# usbkeyboard1.net
KiCad netlist of a schematic drawn in EAGLE
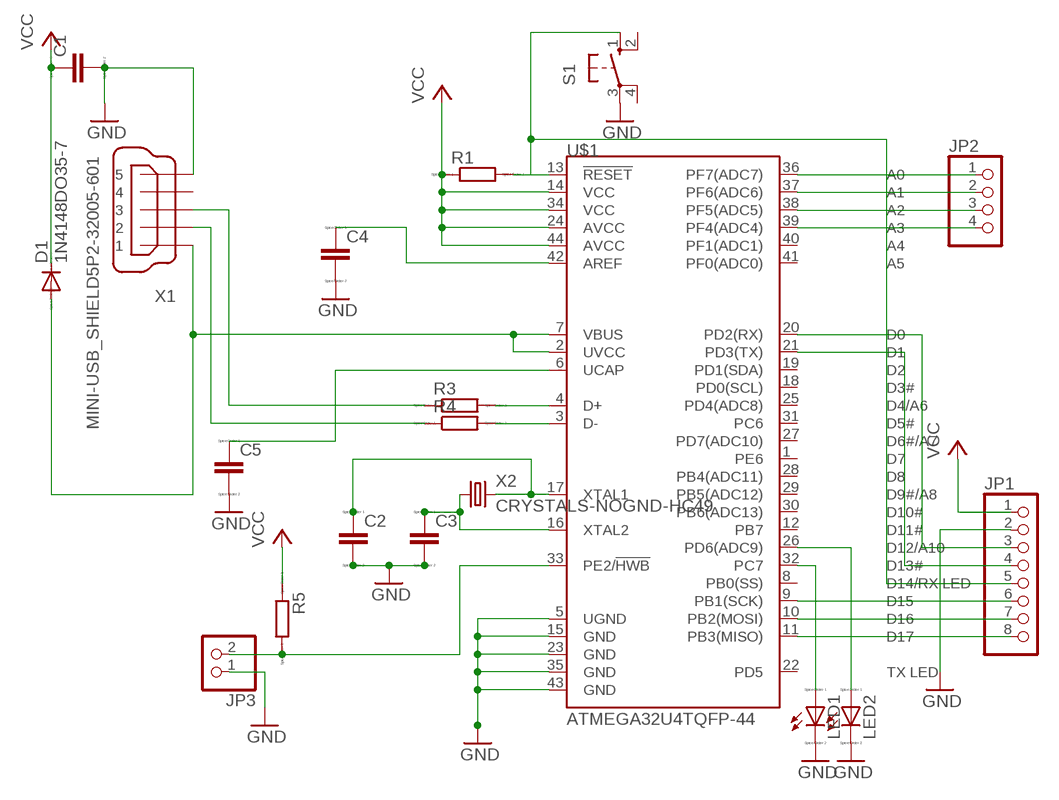
[diagram p0: schematic, sheet 1]

(export (version "E")
  (design (tool "Eeschema 10.0.6"))
  (components
    (comp (ref "C1")
      (value "CC0603")
      (footprint "eagle-import:C0603")
      (libsource (lib "eagle-import") (part "CC0603"))
    )
    (comp (ref "C2")
      (value "CC0603")
      (footprint "eagle-import:C0603")
      (libsource (lib "eagle-import") (part "CC0603"))
    )
    (comp (ref "C3")
      (value "CC0603")
      (footprint "eagle-import:C0603")
      (libsource (lib "eagle-import") (part "CC0603"))
    )
    (comp (ref "C4")
      (value "CC0603")
      (footprint "eagle-import:C0603")
      (libsource (lib "eagle-import") (part "CC0603"))
    )
    (comp (ref "C5")
      (value "CC0603")
      (footprint "eagle-import:C0603")
      (libsource (lib "eagle-import") (part "CC0603"))
    )
    (comp (ref "D1")
      (value "1N4148DO35-7")
      (footprint "eagle-import:DO35-7")
      (libsource (lib "eagle-import") (part "1N4148DO35-7"))
    )
    (comp (ref "JP1")
      (value "PINHD-1X8")
      (footprint "eagle-import:1X08")
      (libsource (lib "eagle-import") (part "PINHD-1X8"))
    )
    (comp (ref "JP2")
      (value "PINHD-1X4")
      (footprint "eagle-import:1X04")
      (libsource (lib "eagle-import") (part "PINHD-1X4"))
    )
    (comp (ref "JP3")
      (value "PINHD-1X2")
      (footprint "eagle-import:1X02")
      (libsource (lib "eagle-import") (part "PINHD-1X2"))
    )
    (comp (ref "LED1")
      (value "LED_ELD260")
      (footprint "eagle-import:LED_LD260")
      (libsource (lib "eagle-import") (part "LED_ELD260"))
    )
    (comp (ref "LED2")
      (value "LED_ELD260")
      (footprint "eagle-import:LED_LD260")
      (libsource (lib "eagle-import") (part "LED_ELD260"))
    )
    (comp (ref "R1")
      (value "RR0603")
      (footprint "eagle-import:R0603")
      (libsource (lib "eagle-import") (part "RR0603"))
    )
    (comp (ref "R3")
      (value "RR0603")
      (footprint "eagle-import:R0603")
      (libsource (lib "eagle-import") (part "RR0603"))
    )
    (comp (ref "R4")
      (value "RR0603")
      (footprint "eagle-import:R0603")
      (libsource (lib "eagle-import") (part "RR0603"))
    )
    (comp (ref "R5")
      (value "RR0603")
      (footprint "eagle-import:R0603")
      (libsource (lib "eagle-import") (part "RR0603"))
    )
    (comp (ref "S1")
      (value "10-XX")
      (footprint "eagle-import:B3F-10XX")
      (fields (field (name "MPN") "B3F-1000"))
      (libsource (lib "eagle-import") (part "10-XX"))
    )
    (comp (ref "U$1")
      (value "ATMEGA32U4TQFP-44")
      (footprint "eagle-import:TQFP44")
      (libsource (lib "eagle-import") (part "ATMEGA32U4TQFP-44"))
    )
    (comp (ref "X1")
      (value "MINI-USB_SHIELD5P2-32005-601")
      (footprint "eagle-import:32005-601")
      (libsource (lib "eagle-import") (part "MINI-USB_SHIELD5P2-32005-601"))
    )
    (comp (ref "X2")
      (value "CRYSTALS-NOGND-HC49")
      (footprint "eagle-import:HC49")
      (libsource (lib "eagle-import") (part "CRYSTALS-NOGND-HC49"))
    )
  )
  (nets
    (net (code "1") (name "GND") (class "Default")
      (node (ref "C1") (pin "2") (pinfunction "2_2") (pintype "passive"))
      (node (ref "C2") (pin "2") (pinfunction "2_2") (pintype "passive"))
      (node (ref "C3") (pin "2") (pinfunction "2_2") (pintype "passive"))
      (node (ref "C4") (pin "2") (pinfunction "2_2") (pintype "passive"))
      (node (ref "C5") (pin "2") (pinfunction "2_2") (pintype "passive"))
      (node (ref "JP1") (pin "2") (pinfunction "2_2") (pintype "passive"))
      (node (ref "JP3") (pin "1") (pinfunction "1_1") (pintype "passive"))
      (node (ref "LED1") (pin "K") (pinfunction "C_K") (pintype "passive"))
      (node (ref "LED2") (pin "K") (pinfunction "C_K") (pintype "passive"))
      (node (ref "S1") (pin "3") (pinfunction "P_3") (pintype "passive"))
      (node (ref "U$1") (pin "15") (pinfunction "GND_15") (pintype "bidirectional"))
      (node (ref "U$1") (pin "23") (pinfunction "GND_23") (pintype "bidirectional"))
      (node (ref "U$1") (pin "35") (pinfunction "GND_35") (pintype "bidirectional"))
      (node (ref "U$1") (pin "43") (pinfunction "GND_43") (pintype "bidirectional"))
      (node (ref "U$1") (pin "5") (pinfunction "UGND_5") (pintype "bidirectional"))
      (node (ref "X1") (pin "5") (pinfunction "5_5") (pintype "passive"))
    )
    (net (code "2") (name "Net-(R3-Pad1)") (class "Default")
      (node (ref "R3") (pin "1") (pinfunction "1_1") (pintype "passive"))
      (node (ref "X1") (pin "3") (pinfunction "3_3") (pintype "passive"))
    )
    (net (code "3") (name "Net-(R4-Pad1)") (class "Default")
      (node (ref "R4") (pin "1") (pinfunction "1_1") (pintype "passive"))
      (node (ref "X1") (pin "2") (pinfunction "2_2") (pintype "passive"))
    )
    (net (code "4") (name "Net-(S1-S)") (class "Default")
      (node (ref "JP1") (pin "5") (pinfunction "5_5") (pintype "passive"))
      (node (ref "R1") (pin "2") (pinfunction "2_2") (pintype "passive"))
      (node (ref "S1") (pin "1") (pinfunction "S_1") (pintype "passive"))
      (node (ref "U$1") (pin "13") (pinfunction "~{RESET}_13") (pintype "bidirectional"))
    )
    (net (code "5") (name "Net-(U$1-AREF)") (class "Default")
      (node (ref "C4") (pin "1") (pinfunction "1_1") (pintype "passive"))
      (node (ref "U$1") (pin "42") (pinfunction "AREF_42") (pintype "bidirectional"))
    )
    (net (code "6") (name "Net-(U$1-D+)") (class "Default")
      (node (ref "R3") (pin "2") (pinfunction "2_2") (pintype "passive"))
      (node (ref "U$1") (pin "4") (pinfunction "D+_4") (pintype "bidirectional"))
    )
    (net (code "7") (name "Net-(U$1-D-)") (class "Default")
      (node (ref "R4") (pin "2") (pinfunction "2_2") (pintype "passive"))
      (node (ref "U$1") (pin "3") (pinfunction "D-_3") (pintype "bidirectional"))
    )
    (net (code "8") (name "Net-(U$1-PB1(SCK))") (class "Default")
      (node (ref "JP1") (pin "6") (pinfunction "6_6") (pintype "passive"))
      (node (ref "U$1") (pin "9") (pinfunction "PB1(SCK)_9") (pintype "bidirectional"))
    )
    (net (code "9") (name "Net-(U$1-PB2(MOSI))") (class "Default")
      (node (ref "JP1") (pin "7") (pinfunction "7_7") (pintype "passive"))
      (node (ref "U$1") (pin "10") (pinfunction "PB2(MOSI)_10") (pintype "bidirectional"))
    )
    (net (code "10") (name "Net-(U$1-PB3(MISO))") (class "Default")
      (node (ref "JP1") (pin "8") (pinfunction "8_8") (pintype "passive"))
      (node (ref "U$1") (pin "11") (pinfunction "PB3(MISO)_11") (pintype "bidirectional"))
    )
    (net (code "11") (name "Net-(U$1-PC7)") (class "Default")
      (node (ref "LED1") (pin "A") (pinfunction "A_A") (pintype "passive"))
      (node (ref "U$1") (pin "32") (pinfunction "PC7_32") (pintype "bidirectional"))
    )
    (net (code "12") (name "Net-(U$1-PD2(RX))") (class "Default")
      (node (ref "JP1") (pin "3") (pinfunction "3_3") (pintype "passive"))
      (node (ref "U$1") (pin "20") (pinfunction "PD2(RX)_20") (pintype "bidirectional"))
    )
    (net (code "13") (name "Net-(U$1-PD3(TX))") (class "Default")
      (node (ref "JP1") (pin "4") (pinfunction "4_4") (pintype "passive"))
      (node (ref "U$1") (pin "21") (pinfunction "PD3(TX)_21") (pintype "bidirectional"))
    )
    (net (code "14") (name "Net-(U$1-PD6(ADC9))") (class "Default")
      (node (ref "LED2") (pin "A") (pinfunction "A_A") (pintype "passive"))
      (node (ref "U$1") (pin "26") (pinfunction "PD6(ADC9)_26") (pintype "bidirectional"))
    )
    (net (code "15") (name "Net-(U$1-PE2{slash}~{HWB})") (class "Default")
      (node (ref "JP3") (pin "2") (pinfunction "2_2") (pintype "passive"))
      (node (ref "R5") (pin "2") (pinfunction "2_2") (pintype "passive"))
      (node (ref "U$1") (pin "33") (pinfunction "PE2/~{HWB}_33") (pintype "bidirectional"))
    )
    (net (code "16") (name "Net-(U$1-PF4(ADC4))") (class "Default")
      (node (ref "JP2") (pin "4") (pinfunction "4_4") (pintype "passive"))
      (node (ref "U$1") (pin "39") (pinfunction "PF4(ADC4)_39") (pintype "bidirectional"))
    )
    (net (code "17") (name "Net-(U$1-PF5(ADC5))") (class "Default")
      (node (ref "JP2") (pin "3") (pinfunction "3_3") (pintype "passive"))
      (node (ref "U$1") (pin "38") (pinfunction "PF5(ADC5)_38") (pintype "bidirectional"))
    )
    (net (code "18") (name "Net-(U$1-PF6(ADC6))") (class "Default")
      (node (ref "JP2") (pin "2") (pinfunction "2_2") (pintype "passive"))
      (node (ref "U$1") (pin "37") (pinfunction "PF6(ADC6)_37") (pintype "bidirectional"))
    )
    (net (code "19") (name "Net-(U$1-PF7(ADC7))") (class "Default")
      (node (ref "JP2") (pin "1") (pinfunction "1_1") (pintype "passive"))
      (node (ref "U$1") (pin "36") (pinfunction "PF7(ADC7)_36") (pintype "bidirectional"))
    )
    (net (code "20") (name "Net-(U$1-UCAP)") (class "Default")
      (node (ref "C5") (pin "1") (pinfunction "1_1") (pintype "passive"))
      (node (ref "U$1") (pin "6") (pinfunction "UCAP_6") (pintype "bidirectional"))
    )
    (net (code "21") (name "Net-(U$1-UVCC)") (class "Default")
      (node (ref "D1") (pin "A") (pinfunction "A_A") (pintype "passive"))
      (node (ref "U$1") (pin "2") (pinfunction "UVCC_2") (pintype "bidirectional"))
      (node (ref "U$1") (pin "7") (pinfunction "VBUS_7") (pintype "bidirectional"))
      (node (ref "X1") (pin "1") (pinfunction "1_1") (pintype "passive"))
    )
    (net (code "22") (name "Net-(U$1-XTAL1)") (class "Default")
      (node (ref "C2") (pin "1") (pinfunction "1_1") (pintype "passive"))
      (node (ref "U$1") (pin "17") (pinfunction "XTAL1_17") (pintype "bidirectional"))
      (node (ref "X2") (pin "2") (pinfunction "2_2") (pintype "passive"))
    )
    (net (code "23") (name "Net-(U$1-XTAL2)") (class "Default")
      (node (ref "C3") (pin "1") (pinfunction "1_1") (pintype "passive"))
      (node (ref "U$1") (pin "16") (pinfunction "XTAL2_16") (pintype "bidirectional"))
      (node (ref "X2") (pin "1") (pinfunction "1_1") (pintype "passive"))
    )
    (net (code "24") (name "VCC") (class "Default")
      (node (ref "C1") (pin "1") (pinfunction "1_1") (pintype "passive"))
      (node (ref "D1") (pin "C") (pinfunction "C_C") (pintype "passive"))
      (node (ref "JP1") (pin "1") (pinfunction "1_1") (pintype "passive"))
      (node (ref "R1") (pin "1") (pinfunction "1_1") (pintype "passive"))
      (node (ref "R5") (pin "1") (pinfunction "1_1") (pintype "passive"))
      (node (ref "U$1") (pin "14") (pinfunction "VCC_14") (pintype "bidirectional"))
      (node (ref "U$1") (pin "24") (pinfunction "AVCC_24") (pintype "bidirectional"))
      (node (ref "U$1") (pin "34") (pinfunction "VCC_34") (pintype "bidirectional"))
      (node (ref "U$1") (pin "44") (pinfunction "AVCC_44") (pintype "bidirectional"))
    )
    (net (code "25") (name "unconnected-(S1-P1-Pad4)") (class "Default")
      (node (ref "S1") (pin "4") (pinfunction "P1_4") (pintype "passive"))
    )
    (net (code "26") (name "unconnected-(S1-S1-Pad2)") (class "Default")
      (node (ref "S1") (pin "2") (pinfunction "S1_2") (pintype "passive"))
    )
    (net (code "27") (name "unconnected-(U$1-PB0(SS)-Pad8)") (class "Default")
      (node (ref "U$1") (pin "8") (pinfunction "PB0(SS)_8") (pintype "bidirectional"))
    )
    (net (code "28") (name "unconnected-(U$1-PB4(ADC11)-Pad28)") (class "Default")
      (node (ref "U$1") (pin "28") (pinfunction "PB4(ADC11)_28") (pintype "bidirectional"))
    )
    (net (code "29") (name "unconnected-(U$1-PB5(ADC12)-Pad29)") (class "Default")
      (node (ref "U$1") (pin "29") (pinfunction "PB5(ADC12)_29") (pintype "bidirectional"))
    )
    (net (code "30") (name "unconnected-(U$1-PB6(ADC13)-Pad30)") (class "Default")
      (node (ref "U$1") (pin "30") (pinfunction "PB6(ADC13)_30") (pintype "bidirectional"))
    )
    (net (code "31") (name "unconnected-(U$1-PB7-Pad12)") (class "Default")
      (node (ref "U$1") (pin "12") (pinfunction "PB7_12") (pintype "bidirectional"))
    )
    (net (code "32") (name "unconnected-(U$1-PC6-Pad31)") (class "Default")
      (node (ref "U$1") (pin "31") (pinfunction "PC6_31") (pintype "bidirectional"))
    )
    (net (code "33") (name "unconnected-(U$1-PD0(SCL)-Pad18)") (class "Default")
      (node (ref "U$1") (pin "18") (pinfunction "PD0(SCL)_18") (pintype "bidirectional"))
    )
    (net (code "34") (name "unconnected-(U$1-PD1(SDA)-Pad19)") (class "Default")
      (node (ref "U$1") (pin "19") (pinfunction "PD1(SDA)_19") (pintype "bidirectional"))
    )
    (net (code "35") (name "unconnected-(U$1-PD4(ADC8)-Pad25)") (class "Default")
      (node (ref "U$1") (pin "25") (pinfunction "PD4(ADC8)_25") (pintype "bidirectional"))
    )
    (net (code "36") (name "unconnected-(U$1-PD5-Pad22)") (class "Default")
      (node (ref "U$1") (pin "22") (pinfunction "PD5_22") (pintype "bidirectional"))
    )
    (net (code "37") (name "unconnected-(U$1-PD7(ADC10)-Pad27)") (class "Default")
      (node (ref "U$1") (pin "27") (pinfunction "PD7(ADC10)_27") (pintype "bidirectional"))
    )
    (net (code "38") (name "unconnected-(U$1-PE6-Pad1)") (class "Default")
      (node (ref "U$1") (pin "1") (pinfunction "PE6_1") (pintype "bidirectional"))
    )
    (net (code "39") (name "unconnected-(U$1-PF0(ADC0)-Pad41)") (class "Default")
      (node (ref "U$1") (pin "41") (pinfunction "PF0(ADC0)_41") (pintype "bidirectional"))
    )
    (net (code "40") (name "unconnected-(U$1-PF1(ADC1)-Pad40)") (class "Default")
      (node (ref "U$1") (pin "40") (pinfunction "PF1(ADC1)_40") (pintype "bidirectional"))
    )
    (net (code "41") (name "unconnected-(X1-Pad4)") (class "Default")
      (node (ref "X1") (pin "4") (pinfunction "4_4") (pintype "passive"))
    )
  )
)
